# MSP-EXP430F5529LP_2.net
KiCad netlist of a schematic drawn in Altium Designer
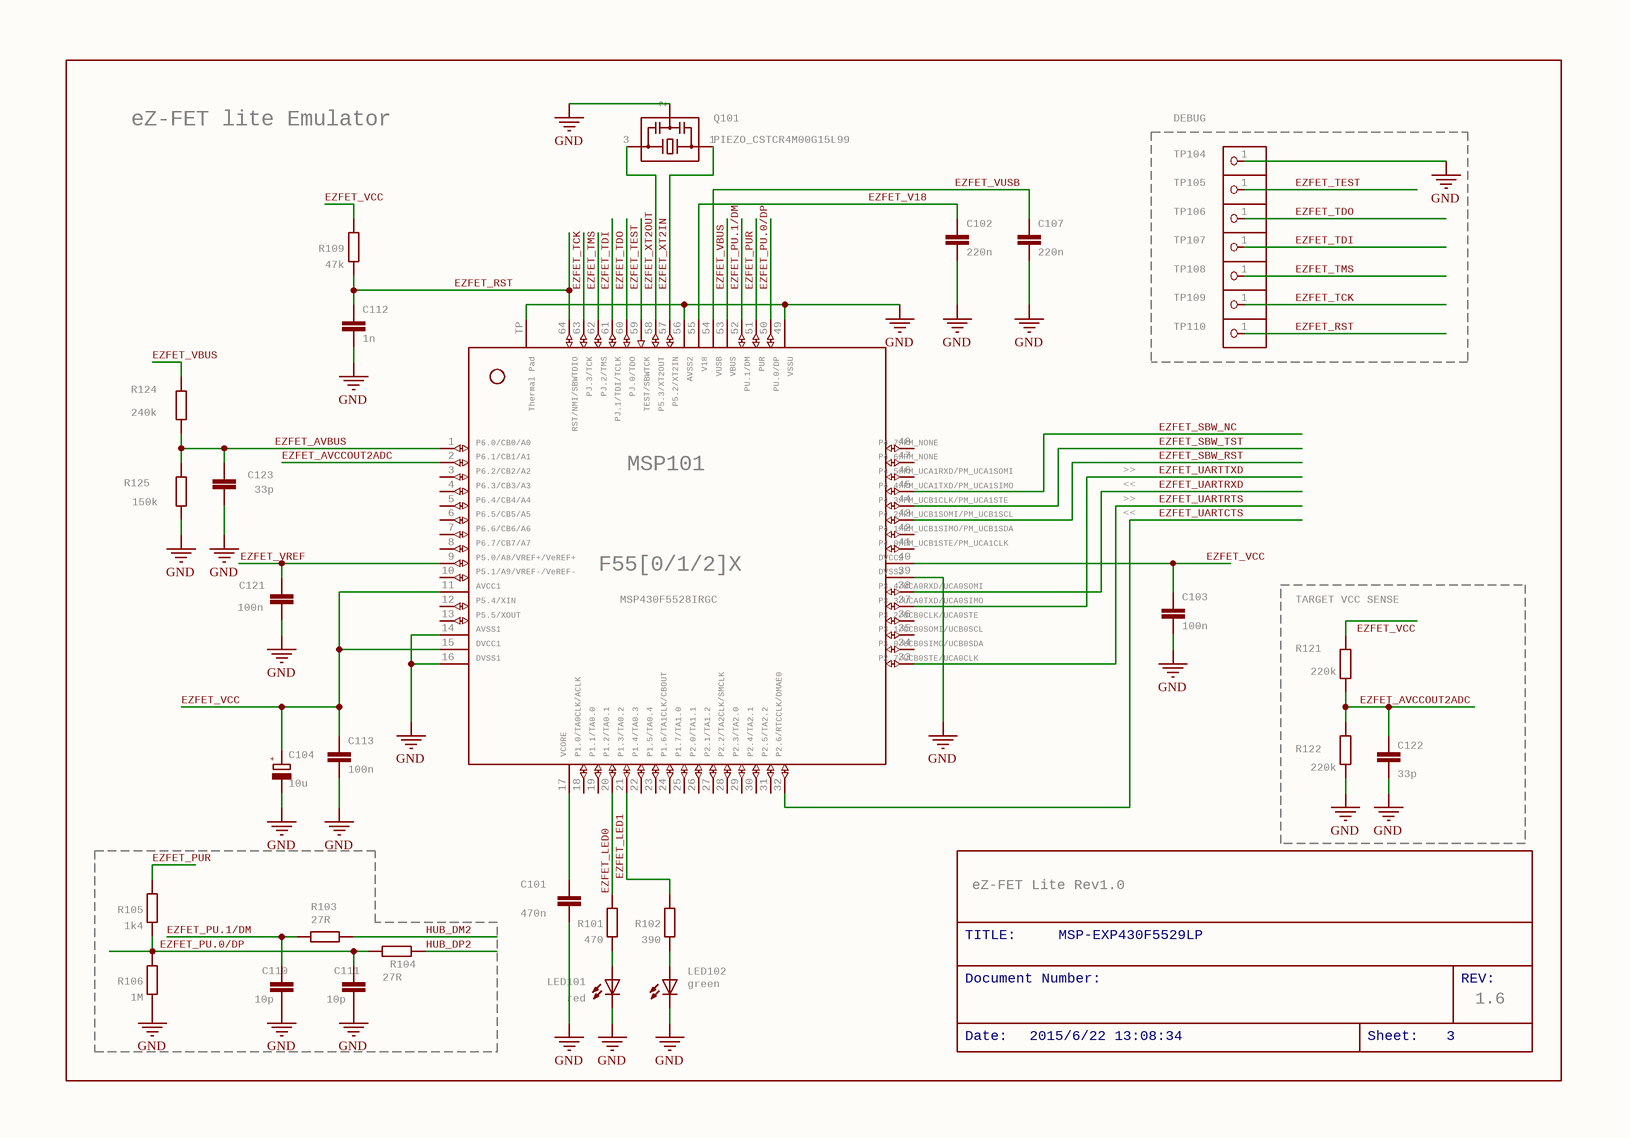
[diagram p0: MSP-EXP430F5529LP_2.SchDoc]

(export (version "E")
  (design (tool "Eeschema 10.0.6"))
  (components
    (comp (ref "C101")
      (value "470n")
      (footprint "0402")
      (description "CAPACITOR, European symbol")
      (libsource (lib "rcl") (part "C-EUCM0402"))
    )
    (comp (ref "C102")
      (value "220n")
      (footprint "0402")
      (description "CAPACITOR, European symbol")
      (libsource (lib "rcl") (part "C-EUCM0402"))
    )
    (comp (ref "C103")
      (value "100n")
      (footprint "0402")
      (description "CAPACITOR, European symbol")
      (libsource (lib "rcl") (part "C-EUCM0402"))
    )
    (comp (ref "C104")
      (value "10u")
      (footprint "A/3216-18R")
      (description "POLARIZED CAPACITOR, European symbol")
      (fields (field (name "+") "+"))
      (libsource (lib "rcl") (part "CPOL-EUA/3216-18R"))
    )
    (comp (ref "C107")
      (value "220n")
      (footprint "0402")
      (description "CAPACITOR, European symbol")
      (libsource (lib "rcl") (part "C-EUCM0402"))
    )
    (comp (ref "C110")
      (value "10p")
      (footprint "0402")
      (description "CAPACITOR, European symbol")
      (libsource (lib "rcl") (part "C-EUCM0402"))
    )
    (comp (ref "C111")
      (value "10p")
      (footprint "0402")
      (description "CAPACITOR, European symbol")
      (libsource (lib "rcl") (part "C-EUCM0402"))
    )
    (comp (ref "C112")
      (value "1n")
      (footprint "0402")
      (description "CAPACITOR, European symbol")
      (libsource (lib "rcl") (part "C-EUCM0402"))
    )
    (comp (ref "C113")
      (value "100n")
      (footprint "0402")
      (description "CAPACITOR, European symbol")
      (libsource (lib "rcl") (part "C-EUCM0402"))
    )
    (comp (ref "C121")
      (value "100n")
      (footprint "0402")
      (description "CAPACITOR, European symbol")
      (libsource (lib "rcl") (part "C-EUCM0402"))
    )
    (comp (ref "C122")
      (value "33p")
      (footprint "0402")
      (description "CAPACITOR, European symbol")
      (libsource (lib "") (part "C-EUCM0402_2"))
    )
    (comp (ref "C123")
      (value "33p")
      (footprint "0402")
      (description "CAPACITOR, European symbol")
      (libsource (lib "") (part "C-EUCM0402_1"))
    )
    (comp (ref "LED101")
      (value "red")
      (footprint "CHIP-LED0603")
      (libsource (lib "led") (part "LEDCHIP-LED0603"))
    )
    (comp (ref "LED102")
      (value "green")
      (footprint "CHIP-LED0603")
      (libsource (lib "led") (part "LEDCHIP-LED0603"))
    )
    (comp (ref "MSP101")
      (value "MSP430F5528IRGC")
      (footprint "RGC64")
      (fields
        (field (name "RST/NMI/SBWTDIO") "RST/NMI/SBWTDIO")
        (field (name "PJ.3/TCK") "PJ.3/TCK")
        (field (name "PJ.2/TMS") "PJ.2/TMS")
        (field (name "PJ.1/TDI/TCLK") "PJ.1/TDI/TCLK")
        (field (name "PJ.0/TDO") "PJ.0/TDO")
        (field (name "TEST/SBWTCK") "TEST/SBWTCK")
        (field (name "P5.3/XT2OUT") "P5.3/XT2OUT")
        (field (name "P5.2/XT2IN") "P5.2/XT2IN")
        (field (name "AVSS2") "AVSS2")
        (field (name "V18") "V18")
        (field (name "VUSB") "VUSB")
        (field (name "VBUS") "VBUS")
        (field (name "PU.1/DM") "PU.1/DM")
        (field (name "PUR") "PUR")
        (field (name "PU.0/DP") "PU.0/DP")
        (field (name "VSSU") "VSSU")
        (field (name "P6.0/CB0/A0") "P6.0/CB0/A0")
        (field (name "P6.1/CB1/A1") "P6.1/CB1/A1")
        (field (name "P6.2/CB2/A2") "P6.2/CB2/A2")
        (field (name "P6.3/CB3/A3") "P6.3/CB3/A3")
        (field (name "P6.4/CB4/A4") "P6.4/CB4/A4")
        (field (name "P6.5/CB5/A5") "P6.5/CB5/A5")
        (field (name "P6.6/CB6/A6") "P6.6/CB6/A6")
        (field (name "P6.7/CB7/A7") "P6.7/CB7/A7")
        (field (name "P5.0/A8/VREF+/VEREF+") "P5.0/A8/VREF+/VeREF+")
        (field (name "P5.1/A9/VREF-/VEREF-") "P5.1/A9/VREF-/VeREF-")
        (field (name "AVCC1") "AVCC1")
        (field (name "P5.4/XIN") "P5.4/XIN")
        (field (name "P5.5/XOUT") "P5.5/XOUT")
        (field (name "AVSS1") "AVSS1")
        (field (name "DVCC1") "DVCC1")
        (field (name "DVSS1") "DVSS1")
        (field (name "VCORE") "VCORE")
        (field (name "P1.0/TA0CLK/ACLK") "P1.0/TA0CLK/ACLK")
        (field (name "P1.1/TA0.0") "P1.1/TA0.0")
        (field (name "P1.2/TA0.1") "P1.2/TA0.1")
        (field (name "P1.3/TA0.2") "P1.3/TA0.2")
        (field (name "P1.4/TA0.3") "P1.4/TA0.3")
        (field (name "P1.5/TA0.4") "P1.5/TA0.4")
        (field (name "P1.6/TA1CLK/CBOUT") "P1.6/TA1CLK/CBOUT")
        (field (name "P1.7/TA1.0") "P1.7/TA1.0")
        (field (name "P2.0/TA1.1") "P2.0/TA1.1")
        (field (name "P2.1/TA1.2") "P2.1/TA1.2")
        (field (name "P2.2/TA2CLK/SMCLK") "P2.2/TA2CLK/SMCLK")
        (field (name "P2.3/TA2.0") "P2.3/TA2.0")
        (field (name "P2.4/TA2.1") "P2.4/TA2.1")
        (field (name "P2.5/TA2.2") "P2.5/TA2.2")
        (field (name "P2.6/RTCCLK/DMAE0") "P2.6/RTCCLK/DMAE0")
        (field (name "P4.7/PM_NONE") "P4.7/PM_NONE")
        (field (name "P4.6/PM_NONE") "P4.6/PM_NONE")
        (field (name "P4.5/PM_UCA1RXD/PM_UCA1SOMI") "P4.5/PM_UCA1RXD/PM_UCA1SOMI")
        (field (name "P4.4/PM_UCA1TXD/PM_UCA1SIMO") "P4.4/PM_UCA1TXD/PM_UCA1SIMO")
        (field (name "P4.3/PM_UCB1CLK/PM_UCA1STE") "P4.3/PM_UCB1CLK/PM_UCA1STE")
        (field (name "P4.2/PM_UCB1SOMI/PM_UCB1SCL") "P4.2/PM_UCB1SOMI/PM_UCB1SCL")
        (field (name "P4.1/PM_UCB1SIMO/PM_UCB1SDA") "P4.1/PM_UCB1SIMO/PM_UCB1SDA")
        (field (name "P4.0/PM_UCB1STE/PM_UCA1CLK") "P4.0/PM_UCB1STE/PM_UCA1CLK")
        (field (name "DVCC2") "DVCC2")
        (field (name "DVSS2") "DVSS2")
        (field (name "P3.4/UCA0RXD/UCA0SOMI") "P3.4/UCA0RXD/UCA0SOMI")
        (field (name "P3.3/UCA0TXD/UCA0SIMO") "P3.3/UCA0TXD/UCA0SIMO")
        (field (name "P3.2/UCB0CLK/UCA0STE") "P3.2/UCB0CLK/UCA0STE")
        (field (name "P3.1/UCB0SOMI/UCB0SCL") "P3.1/UCB0SOMI/UCB0SCL")
        (field (name "P3.0/UCB0SIMO/UCB0SDA") "P3.0/UCB0SIMO/UCB0SDA")
        (field (name "P2.7/UCB0STE/UCA0CLK") "P2.7/UCB0STE/UCA0CLK")
        (field (name "F55[0/1/2]X") "F55[0/1/2]X")
        (field (name "THERMALPAD") "Thermal Pad")
        (field (name "LIBRARYNAME") "TI_MSP430_v16_intern")
      )
      (libsource (lib "TI_MSP430_v16_intern") (part "F55[0/1/2]X---RGC64"))
    )
    (comp (ref "Q101")
      (value "PIEZO_CSTCR4M00G15L99")
      (footprint "MURATA-FILTER_CSTCR")
      (description "Resonator   Source: murata.co.jp")
      (fields (field (name "MF") "MF") (field (name "MPN") "CSTCR6M00G53-R0"))
      (libsource (lib "murata") (part "MURATA-FILTER_CSTCR"))
    )
    (comp (ref "R101")
      (value "470")
      (footprint "0402")
      (description "RESISTOR, European symbol")
      (libsource (lib "rcl") (part "R-EU_RM0402"))
    )
    (comp (ref "R102")
      (value "390")
      (footprint "0402")
      (description "RESISTOR, European symbol")
      (libsource (lib "rcl") (part "R-EU_RM0402"))
    )
    (comp (ref "R103")
      (value "27R")
      (footprint "0402")
      (description "RESISTOR, European symbol")
      (libsource (lib "rcl") (part "R-EU_RM0402"))
    )
    (comp (ref "R104")
      (value "27R")
      (footprint "0402")
      (description "RESISTOR, European symbol")
      (libsource (lib "rcl") (part "R-EU_RM0402"))
    )
    (comp (ref "R105")
      (value "1k4")
      (footprint "0402")
      (description "RESISTOR, European symbol")
      (libsource (lib "rcl") (part "R-EU_RM0402"))
    )
    (comp (ref "R106")
      (value "1M")
      (footprint "0402")
      (description "RESISTOR, European symbol")
      (libsource (lib "rcl") (part "R-EU_RM0402"))
    )
    (comp (ref "R109")
      (value "47k")
      (footprint "0402")
      (description "RESISTOR, European symbol")
      (libsource (lib "rcl") (part "R-EU_RM0402"))
    )
    (comp (ref "R121")
      (value "220k")
      (footprint "0402")
      (description "RESISTOR, European symbol")
      (libsource (lib "rcl") (part "R-EU_RM0402"))
    )
    (comp (ref "R122")
      (value "220k")
      (footprint "0402")
      (description "RESISTOR, European symbol")
      (libsource (lib "rcl") (part "R-EU_RM0402"))
    )
    (comp (ref "R124")
      (value "240k")
      (footprint "0402")
      (description "RESISTOR, European symbol")
      (libsource (lib "rcl") (part "R-EU_RM0402"))
    )
    (comp (ref "R125")
      (value "150k")
      (footprint "0402")
      (description "RESISTOR, European symbol")
      (libsource (lib "rcl") (part "R-EU_RM0402"))
    )
    (comp (ref "TP104")
      (value "TEST_PIN2")
      (footprint "1X01")
      (description "PIN HEADER")
      (fields (field (name "LIBRARYNAME") "pinhead"))
      (libsource (lib "pinhead") (part "PINHD-1X1"))
    )
    (comp (ref "TP105")
      (value "TEST_PIN2")
      (footprint "1X01")
      (description "PIN HEADER")
      (fields (field (name "LIBRARYNAME") "pinhead"))
      (libsource (lib "pinhead") (part "PINHD-1X1"))
    )
    (comp (ref "TP106")
      (value "TEST_PIN2")
      (footprint "1X01")
      (description "PIN HEADER")
      (fields (field (name "LIBRARYNAME") "pinhead"))
      (libsource (lib "pinhead") (part "PINHD-1X1"))
    )
    (comp (ref "TP107")
      (value "TEST_PIN2")
      (footprint "1X01")
      (description "PIN HEADER")
      (fields (field (name "LIBRARYNAME") "pinhead"))
      (libsource (lib "pinhead") (part "PINHD-1X1"))
    )
    (comp (ref "TP108")
      (value "TEST_PIN2")
      (footprint "1X01")
      (description "PIN HEADER")
      (fields (field (name "LIBRARYNAME") "pinhead"))
      (libsource (lib "pinhead") (part "PINHD-1X1"))
    )
    (comp (ref "TP109")
      (value "TEST_PIN2")
      (footprint "1X01")
      (description "PIN HEADER")
      (fields (field (name "LIBRARYNAME") "pinhead"))
      (libsource (lib "pinhead") (part "PINHD-1X1"))
    )
    (comp (ref "TP110")
      (value "TEST_PIN2")
      (footprint "1X01")
      (description "PIN HEADER")
      (fields (field (name "LIBRARYNAME") "pinhead"))
      (libsource (lib "pinhead") (part "PINHD-1X1"))
    )
  )
  (nets
    (net (code "1") (name "/EZFET_AVBUS") (class "Default")
      (node (ref "C123") (pin "2") (pinfunction "2_2") (pintype "passive"))
      (node (ref "MSP101") (pin "1") (pinfunction "1_1") (pintype "bidirectional"))
      (node (ref "R124") (pin "2") (pinfunction "2_2") (pintype "passive"))
      (node (ref "R125") (pin "1") (pinfunction "1_1") (pintype "passive"))
    )
    (net (code "2") (name "/EZFET_AVCCOUT2ADC") (class "Default")
      (node (ref "C122") (pin "2") (pinfunction "2_2") (pintype "passive"))
      (node (ref "MSP101") (pin "2") (pinfunction "2_2") (pintype "bidirectional"))
      (node (ref "R121") (pin "2") (pinfunction "2_2") (pintype "passive"))
      (node (ref "R122") (pin "1") (pinfunction "1_1") (pintype "passive"))
    )
    (net (code "3") (name "/EZFET_LED0") (class "Default")
      (node (ref "MSP101") (pin "20") (pinfunction "20_20") (pintype "bidirectional"))
      (node (ref "R101") (pin "2") (pinfunction "2_2") (pintype "passive"))
    )
    (net (code "4") (name "/EZFET_LED1") (class "Default")
      (node (ref "MSP101") (pin "21") (pinfunction "21_21") (pintype "bidirectional"))
      (node (ref "R102") (pin "2") (pinfunction "2_2") (pintype "passive"))
    )
    (net (code "5") (name "/EZFET_PU.0{slash}DP") (class "Default")
      (node (ref "C111") (pin "1") (pinfunction "1_1") (pintype "passive"))
      (node (ref "MSP101") (pin "50") (pinfunction "50_50") (pintype "bidirectional"))
      (node (ref "R104") (pin "2") (pinfunction "2_2") (pintype "passive"))
      (node (ref "R105") (pin "1") (pinfunction "1_1") (pintype "passive"))
      (node (ref "R106") (pin "2") (pinfunction "2_2") (pintype "passive"))
    )
    (net (code "6") (name "/EZFET_PU.1{slash}DM") (class "Default")
      (node (ref "C110") (pin "1") (pinfunction "1_1") (pintype "passive"))
      (node (ref "MSP101") (pin "52") (pinfunction "52_52") (pintype "bidirectional"))
      (node (ref "R103") (pin "2") (pinfunction "2_2") (pintype "passive"))
    )
    (net (code "7") (name "/EZFET_PUR") (class "Default")
      (node (ref "MSP101") (pin "51") (pinfunction "51_51") (pintype "bidirectional"))
      (node (ref "R105") (pin "2") (pinfunction "2_2") (pintype "passive"))
    )
    (net (code "8") (name "/EZFET_RST") (class "Default")
      (node (ref "C112") (pin "1") (pinfunction "1_1") (pintype "passive"))
      (node (ref "MSP101") (pin "64") (pinfunction "64_64") (pintype "bidirectional"))
      (node (ref "R109") (pin "1") (pinfunction "1_1") (pintype "passive"))
      (node (ref "TP110") (pin "1") (pinfunction "1_1") (pintype "passive"))
    )
    (net (code "9") (name "/EZFET_SBW_NC") (class "Default")
      (node (ref "MSP101") (pin "45") (pinfunction "45_45") (pintype "bidirectional"))
    )
    (net (code "10") (name "/EZFET_SBW_RST") (class "Default")
      (node (ref "MSP101") (pin "43") (pinfunction "43_43") (pintype "bidirectional"))
    )
    (net (code "11") (name "/EZFET_SBW_TST") (class "Default")
      (node (ref "MSP101") (pin "44") (pinfunction "44_44") (pintype "bidirectional"))
    )
    (net (code "12") (name "/EZFET_TCK") (class "Default")
      (node (ref "MSP101") (pin "63") (pinfunction "63_63") (pintype "bidirectional"))
      (node (ref "TP109") (pin "1") (pinfunction "1_1") (pintype "passive"))
    )
    (net (code "13") (name "/EZFET_TDI") (class "Default")
      (node (ref "MSP101") (pin "61") (pinfunction "61_61") (pintype "bidirectional"))
      (node (ref "TP107") (pin "1") (pinfunction "1_1") (pintype "passive"))
    )
    (net (code "14") (name "/EZFET_TDO") (class "Default")
      (node (ref "MSP101") (pin "60") (pinfunction "60_60") (pintype "bidirectional"))
      (node (ref "TP106") (pin "1") (pinfunction "1_1") (pintype "passive"))
    )
    (net (code "15") (name "/EZFET_TEST") (class "Default")
      (node (ref "MSP101") (pin "59") (pinfunction "59_59") (pintype "input"))
      (node (ref "TP105") (pin "1") (pinfunction "1_1") (pintype "passive"))
    )
    (net (code "16") (name "/EZFET_TMS") (class "Default")
      (node (ref "MSP101") (pin "62") (pinfunction "62_62") (pintype "bidirectional"))
      (node (ref "TP108") (pin "1") (pinfunction "1_1") (pintype "passive"))
    )
    (net (code "17") (name "/EZFET_UARTCTS") (class "Default")
      (node (ref "MSP101") (pin "32") (pinfunction "32_32") (pintype "bidirectional"))
    )
    (net (code "18") (name "/EZFET_UARTRTS") (class "Default")
      (node (ref "MSP101") (pin "33") (pinfunction "33_33") (pintype "bidirectional"))
    )
    (net (code "19") (name "/EZFET_UARTRXD") (class "Default")
      (node (ref "MSP101") (pin "38") (pinfunction "38_38") (pintype "bidirectional"))
    )
    (net (code "20") (name "/EZFET_UARTTXD") (class "Default")
      (node (ref "MSP101") (pin "37") (pinfunction "37_37") (pintype "bidirectional"))
    )
    (net (code "21") (name "/EZFET_V18") (class "Default")
      (node (ref "C102") (pin "1") (pinfunction "1_1") (pintype "passive"))
      (node (ref "MSP101") (pin "55") (pinfunction "55_55") (pintype "power_in"))
    )
    (net (code "22") (name "/EZFET_VBUS") (class "Default")
      (node (ref "MSP101") (pin "53") (pinfunction "53_53") (pintype "power_in"))
      (node (ref "R124") (pin "1") (pinfunction "1_1") (pintype "passive"))
    )
    (net (code "23") (name "/EZFET_VCC") (class "Default")
      (node (ref "C103") (pin "1") (pinfunction "1_1") (pintype "passive"))
      (node (ref "C104") (pin "+") (pinfunction "+_+") (pintype "passive"))
      (node (ref "C113") (pin "1") (pinfunction "1_1") (pintype "passive"))
      (node (ref "MSP101") (pin "11") (pinfunction "11_11") (pintype "power_in"))
      (node (ref "MSP101") (pin "15") (pinfunction "15_15") (pintype "power_in"))
      (node (ref "MSP101") (pin "40") (pinfunction "40_40") (pintype "power_in"))
      (node (ref "R109") (pin "2") (pinfunction "2_2") (pintype "passive"))
      (node (ref "R121") (pin "1") (pinfunction "1_1") (pintype "passive"))
    )
    (net (code "24") (name "/EZFET_VREF") (class "Default")
      (node (ref "C121") (pin "1") (pinfunction "1_1") (pintype "passive"))
      (node (ref "MSP101") (pin "9") (pinfunction "9_9") (pintype "bidirectional"))
    )
    (net (code "25") (name "/EZFET_VUSB") (class "Default")
      (node (ref "C107") (pin "1") (pinfunction "1_1") (pintype "passive"))
      (node (ref "MSP101") (pin "54") (pinfunction "54_54") (pintype "power_in"))
    )
    (net (code "26") (name "/EZFET_XT2IN") (class "Default")
      (node (ref "MSP101") (pin "57") (pinfunction "57_57") (pintype "bidirectional"))
      (node (ref "Q101") (pin "1") (pinfunction "1_1") (pintype "passive"))
    )
    (net (code "27") (name "/EZFET_XT2OUT") (class "Default")
      (node (ref "MSP101") (pin "58") (pinfunction "58_58") (pintype "bidirectional"))
      (node (ref "Q101") (pin "3") (pinfunction "3_3") (pintype "passive"))
    )
    (net (code "28") (name "/HUB_DM2") (class "Default")
      (node (ref "R103") (pin "1") (pinfunction "1_1") (pintype "passive"))
    )
    (net (code "29") (name "/HUB_DP2") (class "Default")
      (node (ref "R104") (pin "1") (pinfunction "1_1") (pintype "passive"))
    )
    (net (code "30") (name "GND") (class "Default")
      (node (ref "C101") (pin "2") (pinfunction "2_2") (pintype "passive"))
      (node (ref "C102") (pin "2") (pinfunction "2_2") (pintype "passive"))
      (node (ref "C103") (pin "2") (pinfunction "2_2") (pintype "passive"))
      (node (ref "C104") (pin "-") (pinfunction "-_-") (pintype "passive"))
      (node (ref "C107") (pin "2") (pinfunction "2_2") (pintype "passive"))
      (node (ref "C110") (pin "2") (pinfunction "2_2") (pintype "passive"))
      (node (ref "C111") (pin "2") (pinfunction "2_2") (pintype "passive"))
      (node (ref "C112") (pin "2") (pinfunction "2_2") (pintype "passive"))
      (node (ref "C113") (pin "2") (pinfunction "2_2") (pintype "passive"))
      (node (ref "C121") (pin "2") (pinfunction "2_2") (pintype "passive"))
      (node (ref "C122") (pin "1") (pinfunction "1_1") (pintype "passive"))
      (node (ref "C123") (pin "1") (pinfunction "1_1") (pintype "passive"))
      (node (ref "LED101") (pin "C") (pinfunction "C_C") (pintype "passive"))
      (node (ref "LED102") (pin "C") (pinfunction "C_C") (pintype "passive"))
      (node (ref "MSP101") (pin "14") (pinfunction "14_14") (pintype "power_in"))
      (node (ref "MSP101") (pin "16") (pinfunction "16_16") (pintype "power_in"))
      (node (ref "MSP101") (pin "39") (pinfunction "39_39") (pintype "power_in"))
      (node (ref "MSP101") (pin "49") (pinfunction "49_49") (pintype "power_in"))
      (node (ref "MSP101") (pin "56") (pinfunction "56_56") (pintype "power_in"))
      (node (ref "MSP101") (pin "TP") (pinfunction "TP_TP") (pintype "power_in"))
      (node (ref "Q101") (pin "2") (pinfunction "2_2") (pintype "passive"))
      (node (ref "R106") (pin "1") (pinfunction "1_1") (pintype "passive"))
      (node (ref "R122") (pin "2") (pinfunction "2_2") (pintype "passive"))
      (node (ref "R125") (pin "2") (pinfunction "2_2") (pintype "passive"))
      (node (ref "TP104") (pin "1") (pinfunction "1_1") (pintype "passive"))
    )
    (net (code "31") (name "Net-(C101-Pad1)") (class "Default")
      (node (ref "C101") (pin "1") (pinfunction "1_1") (pintype "passive"))
      (node (ref "MSP101") (pin "17") (pinfunction "17_17") (pintype "power_in"))
    )
    (net (code "32") (name "Net-(LED101-PadA)") (class "Default")
      (node (ref "LED101") (pin "A") (pinfunction "A_A") (pintype "passive"))
      (node (ref "R101") (pin "1") (pinfunction "1_1") (pintype "passive"))
    )
    (net (code "33") (name "Net-(LED102-PadA)") (class "Default")
      (node (ref "LED102") (pin "A") (pinfunction "A_A") (pintype "passive"))
      (node (ref "R102") (pin "1") (pinfunction "1_1") (pintype "passive"))
    )
    (net (code "34") (name "unconnected-(MSP101-Pad3)") (class "Default")
      (node (ref "MSP101") (pin "3") (pinfunction "3_3") (pintype "bidirectional"))
    )
    (net (code "35") (name "unconnected-(MSP101-Pad4)") (class "Default")
      (node (ref "MSP101") (pin "4") (pinfunction "4_4") (pintype "bidirectional"))
    )
    (net (code "36") (name "unconnected-(MSP101-Pad5)") (class "Default")
      (node (ref "MSP101") (pin "5") (pinfunction "5_5") (pintype "bidirectional"))
    )
    (net (code "37") (name "unconnected-(MSP101-Pad6)") (class "Default")
      (node (ref "MSP101") (pin "6") (pinfunction "6_6") (pintype "bidirectional"))
    )
    (net (code "38") (name "unconnected-(MSP101-Pad7)") (class "Default")
      (node (ref "MSP101") (pin "7") (pinfunction "7_7") (pintype "bidirectional"))
    )
    (net (code "39") (name "unconnected-(MSP101-Pad8)") (class "Default")
      (node (ref "MSP101") (pin "8") (pinfunction "8_8") (pintype "bidirectional"))
    )
    (net (code "40") (name "unconnected-(MSP101-Pad10)") (class "Default")
      (node (ref "MSP101") (pin "10") (pinfunction "10_10") (pintype "bidirectional"))
    )
    (net (code "41") (name "unconnected-(MSP101-Pad12)") (class "Default")
      (node (ref "MSP101") (pin "12") (pinfunction "12_12") (pintype "bidirectional"))
    )
    (net (code "42") (name "unconnected-(MSP101-Pad13)") (class "Default")
      (node (ref "MSP101") (pin "13") (pinfunction "13_13") (pintype "bidirectional"))
    )
    (net (code "43") (name "unconnected-(MSP101-Pad18)") (class "Default")
      (node (ref "MSP101") (pin "18") (pinfunction "18_18") (pintype "bidirectional"))
    )
    (net (code "44") (name "unconnected-(MSP101-Pad19)") (class "Default")
      (node (ref "MSP101") (pin "19") (pinfunction "19_19") (pintype "bidirectional"))
    )
    (net (code "45") (name "unconnected-(MSP101-Pad22)") (class "Default")
      (node (ref "MSP101") (pin "22") (pinfunction "22_22") (pintype "bidirectional"))
    )
    (net (code "46") (name "unconnected-(MSP101-Pad23)") (class "Default")
      (node (ref "MSP101") (pin "23") (pinfunction "23_23") (pintype "bidirectional"))
    )
    (net (code "47") (name "unconnected-(MSP101-Pad24)") (class "Default")
      (node (ref "MSP101") (pin "24") (pinfunction "24_24") (pintype "bidirectional"))
    )
    (net (code "48") (name "unconnected-(MSP101-Pad25)") (class "Default")
      (node (ref "MSP101") (pin "25") (pinfunction "25_25") (pintype "bidirectional"))
    )
    (net (code "49") (name "unconnected-(MSP101-Pad26)") (class "Default")
      (node (ref "MSP101") (pin "26") (pinfunction "26_26") (pintype "bidirectional"))
    )
    (net (code "50") (name "unconnected-(MSP101-Pad27)") (class "Default")
      (node (ref "MSP101") (pin "27") (pinfunction "27_27") (pintype "bidirectional"))
    )
    (net (code "51") (name "unconnected-(MSP101-Pad28)") (class "Default")
      (node (ref "MSP101") (pin "28") (pinfunction "28_28") (pintype "bidirectional"))
    )
    (net (code "52") (name "unconnected-(MSP101-Pad29)") (class "Default")
      (node (ref "MSP101") (pin "29") (pinfunction "29_29") (pintype "bidirectional"))
    )
    (net (code "53") (name "unconnected-(MSP101-Pad30)") (class "Default")
      (node (ref "MSP101") (pin "30") (pinfunction "30_30") (pintype "bidirectional"))
    )
    (net (code "54") (name "unconnected-(MSP101-Pad31)") (class "Default")
      (node (ref "MSP101") (pin "31") (pinfunction "31_31") (pintype "bidirectional"))
    )
    (net (code "55") (name "unconnected-(MSP101-Pad34)") (class "Default")
      (node (ref "MSP101") (pin "34") (pinfunction "34_34") (pintype "bidirectional"))
    )
    (net (code "56") (name "unconnected-(MSP101-Pad35)") (class "Default")
      (node (ref "MSP101") (pin "35") (pinfunction "35_35") (pintype "bidirectional"))
    )
    (net (code "57") (name "unconnected-(MSP101-Pad36)") (class "Default")
      (node (ref "MSP101") (pin "36") (pinfunction "36_36") (pintype "bidirectional"))
    )
    (net (code "58") (name "unconnected-(MSP101-Pad41)") (class "Default")
      (node (ref "MSP101") (pin "41") (pinfunction "41_41") (pintype "bidirectional"))
    )
    (net (code "59") (name "unconnected-(MSP101-Pad42)") (class "Default")
      (node (ref "MSP101") (pin "42") (pinfunction "42_42") (pintype "bidirectional"))
    )
    (net (code "60") (name "unconnected-(MSP101-Pad46)") (class "Default")
      (node (ref "MSP101") (pin "46") (pinfunction "46_46") (pintype "bidirectional"))
    )
    (net (code "61") (name "unconnected-(MSP101-Pad47)") (class "Default")
      (node (ref "MSP101") (pin "47") (pinfunction "47_47") (pintype "bidirectional"))
    )
    (net (code "62") (name "unconnected-(MSP101-Pad48)") (class "Default")
      (node (ref "MSP101") (pin "48") (pinfunction "48_48") (pintype "bidirectional"))
    )
  )
)
